# BATT_CPU.net
KiCad netlist of a schematic drawn in EAGLE
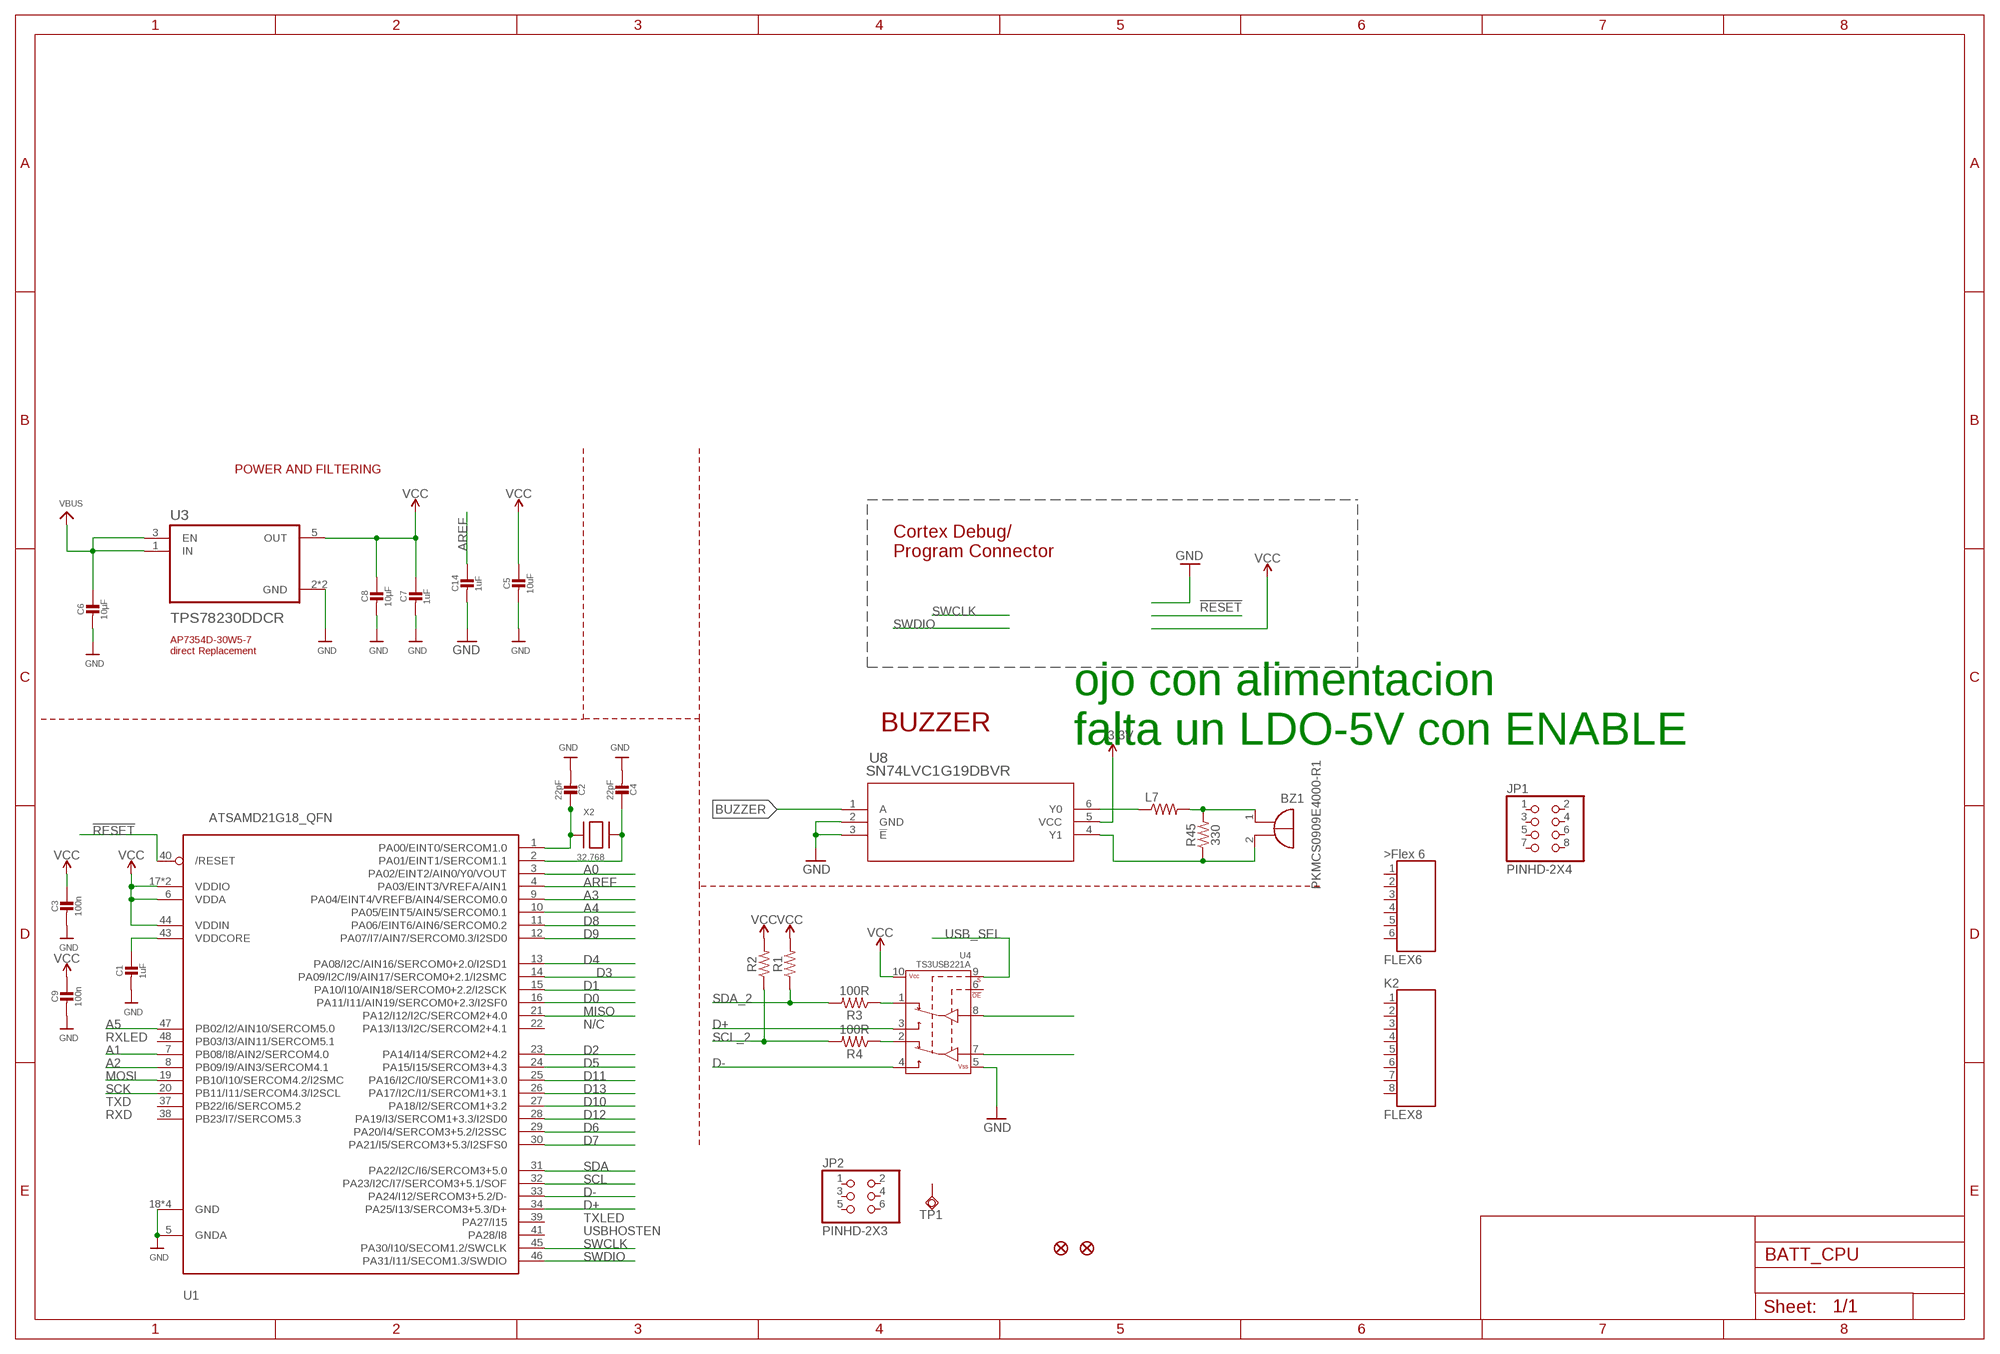
[diagram p0: schematic, sheet 1]

(export (version "E")
  (design (tool "Eeschema 10.0.6"))
  (components
    (comp (ref "BZ1")
      (value "PKMCS0909E4000-R1")
      (footprint "eagle-import:PKMCS0909")
      (libsource (lib "eagle-import") (part "PKMCS0909E4000-R1"))
    )
    (comp (ref "C1")
      (value "1uF")
      (footprint "eagle-import:0603-NO")
      (libsource (lib "eagle-import") (part "CAP_CERAMIC0603_NO"))
    )
    (comp (ref "C2")
      (value "22pF")
      (footprint "eagle-import:0603-NO")
      (libsource (lib "eagle-import") (part "CAP_CERAMIC0603_NO"))
    )
    (comp (ref "C3")
      (value "100n")
      (footprint "eagle-import:0603-NO")
      (libsource (lib "eagle-import") (part "CAP_CERAMIC0603_NO"))
    )
    (comp (ref "C4")
      (value "22pF")
      (footprint "eagle-import:0603-NO")
      (libsource (lib "eagle-import") (part "CAP_CERAMIC0603_NO"))
    )
    (comp (ref "C5")
      (value "10uF")
      (footprint "eagle-import:0805-NO")
      (libsource (lib "eagle-import") (part "CAP_CERAMIC0805-NOOUTLINE"))
    )
    (comp (ref "C6")
      (value "10µF")
      (footprint "eagle-import:0805-NO")
      (libsource (lib "eagle-import") (part "CAP_CERAMIC0805-NOOUTLINE"))
    )
    (comp (ref "C7")
      (value "1uF")
      (footprint "eagle-import:0603-NO")
      (libsource (lib "eagle-import") (part "CAP_CERAMIC0603_NO"))
    )
    (comp (ref "C8")
      (value "10µF")
      (footprint "eagle-import:0805-NO")
      (libsource (lib "eagle-import") (part "CAP_CERAMIC0805-NOOUTLINE"))
    )
    (comp (ref "C9")
      (value "100n")
      (footprint "eagle-import:0603-NO")
      (libsource (lib "eagle-import") (part "CAP_CERAMIC0603_NO"))
    )
    (comp (ref "C14")
      (value "1uF")
      (footprint "eagle-import:0603-NO")
      (libsource (lib "eagle-import") (part "CAP_CERAMIC0603_NO"))
    )
    (comp (ref "JP1")
      (value "PINHD-2X4")
      (footprint "eagle-import:2X04")
      (libsource (lib "eagle-import") (part "PINHD-2X4"))
    )
    (comp (ref "JP2")
      (value "PINHD-2X3")
      (footprint "eagle-import:2X03")
      (libsource (lib "eagle-import") (part "PINHD-2X3"))
    )
    (comp (ref "K1")
      (value "FLEX6")
      (footprint "eagle-import:FLEX6")
      (libsource (lib "eagle-import") (part "FLEX6"))
    )
    (comp (ref "K2")
      (value "FLEX8")
      (footprint "eagle-import:FLEX8")
      (libsource (lib "eagle-import") (part "FLEX8"))
    )
    (comp (ref "L7")
      (value "MMZ2012Y202BT000")
      (footprint "eagle-import:0805")
      (libsource (lib "eagle-import") (part "RESISTOR0805-RES"))
    )
    (comp (ref "R1")
      (value "RESISTOR0603")
      (footprint "eagle-import:0603")
      (libsource (lib "eagle-import") (part "RESISTOR0603"))
    )
    (comp (ref "R2")
      (value "RESISTOR0603")
      (footprint "eagle-import:0603")
      (libsource (lib "eagle-import") (part "RESISTOR0603"))
    )
    (comp (ref "R3")
      (value "100R")
      (footprint "eagle-import:0603")
      (libsource (lib "eagle-import") (part "RESISTOR0603"))
    )
    (comp (ref "R4")
      (value "100R")
      (footprint "eagle-import:0603")
      (libsource (lib "eagle-import") (part "RESISTOR0603"))
    )
    (comp (ref "R45")
      (value "330")
      (footprint "eagle-import:0805")
      (libsource (lib "eagle-import") (part "RESISTOR0805"))
    )
    (comp (ref "TP1")
      (value "TESTPAD_TPSQB1,27")
      (footprint "eagle-import:TESTPAD_B1,27")
      (libsource (lib "eagle-import") (part "TESTPAD_TPSQB1,27"))
    )
    (comp (ref "U$34")
      (value "FIDUCIAL\"\"")
      (footprint "eagle-import:FIDUCIAL_1MM")
      (libsource (lib "eagle-import") (part "FIDUCIAL{dblquote}{dblquote}"))
    )
    (comp (ref "U$35")
      (value "FIDUCIAL\"\"")
      (footprint "eagle-import:FIDUCIAL_1MM")
      (libsource (lib "eagle-import") (part "FIDUCIAL{dblquote}{dblquote}"))
    )
    (comp (ref "U1")
      (value "ATSAMD21G18_QFN")
      (footprint "eagle-import:TQFN48_7MM")
      (libsource (lib "eagle-import") (part "ATSAMD21J_QFN"))
    )
    (comp (ref "U3")
      (value "TPS78230DDCR")
      (footprint "eagle-import:SOT95P280X110-5N")
      (fields (field (name "MF") "Texas Instruments"))
      (libsource (lib "eagle-import") (part "TPS78230DDCR"))
    )
    (comp (ref "U4")
      (value "TS3USB221A")
      (footprint "eagle-import:QFN-10-RSE")
      (libsource (lib "eagle-import") (part "TS3USB221A"))
    )
    (comp (ref "U8")
      (value "SN74LVC1G19DBVR")
      (footprint "eagle-import:DBV6")
      (fields
        (field (name "GENERIC_PART_NUMBER") "SN74LVC1G19")
        (field (name "MANUFACTURER") "Texas Instruments")
      )
      (libsource (lib "eagle-import") (part "SN74LVC1G19DBVR"))
    )
    (comp (ref "X2")
      (value "32.768")
      (footprint "eagle-import:XTAL3215")
      (libsource (lib "eagle-import") (part "XTAL-3.2X1.5"))
    )
  )
  (nets
    (net (code "1") (name "/A0") (class "Default")
      (node (ref "U1") (pin "3") (pinfunction "PA02/EINT2/AIN0/Y0/VOUT_3") (pintype "bidirectional"))
    )
    (net (code "2") (name "/A1") (class "Default")
      (node (ref "U1") (pin "7") (pinfunction "PB08/I8/AIN2/SERCOM4.0_7") (pintype "bidirectional"))
    )
    (net (code "3") (name "/A2") (class "Default")
      (node (ref "U1") (pin "8") (pinfunction "PB09/I9/AIN3/SERCOM4.1_8") (pintype "bidirectional"))
    )
    (net (code "4") (name "/A3") (class "Default")
      (node (ref "U1") (pin "9") (pinfunction "PA04/EINT4/VREFB/AIN4/SERCOM0.0_9") (pintype "bidirectional"))
    )
    (net (code "5") (name "/A4") (class "Default")
      (node (ref "U1") (pin "10") (pinfunction "PA05/EINT5/AIN5/SERCOM0.1_10") (pintype "bidirectional"))
    )
    (net (code "6") (name "/A5") (class "Default")
      (node (ref "U1") (pin "47") (pinfunction "PB02/I2/AIN10/SERCOM5.0_47") (pintype "bidirectional"))
    )
    (net (code "7") (name "/AREF") (class "Default")
      (node (ref "C14") (pin "1") (pinfunction "1_1") (pintype "passive"))
      (node (ref "U1") (pin "4") (pinfunction "PA03/EINT3/VREFA/AIN1_4") (pintype "bidirectional"))
    )
    (net (code "8") (name "/D+") (class "Default")
      (node (ref "U1") (pin "34") (pinfunction "PA25/I13/SERCOM3+5.3/D+_34") (pintype "bidirectional"))
      (node (ref "U4") (pin "3") (pinfunction "2D+_3") (pintype "bidirectional"))
    )
    (net (code "9") (name "/D-") (class "Default")
      (node (ref "U1") (pin "33") (pinfunction "PA24/I12/SERCOM3+5.2/D-_33") (pintype "bidirectional"))
      (node (ref "U4") (pin "4") (pinfunction "2D-_4") (pintype "bidirectional"))
    )
    (net (code "10") (name "/D0") (class "Default")
      (node (ref "U1") (pin "16") (pinfunction "PA11/I11/AIN19/SERCOM0+2.3/I2SF0_16") (pintype "bidirectional"))
    )
    (net (code "11") (name "/D1") (class "Default")
      (node (ref "U1") (pin "15") (pinfunction "PA10/I10/AIN18/SERCOM0+2.2/I2SCK_15") (pintype "bidirectional"))
    )
    (net (code "12") (name "/D2") (class "Default")
      (node (ref "U1") (pin "23") (pinfunction "PA14/I14/SERCOM2+4.2_23") (pintype "bidirectional"))
    )
    (net (code "13") (name "/D3") (class "Default")
      (node (ref "U1") (pin "14") (pinfunction "PA09/I2C/I9/AIN17/SERCOM0+2.1/I2SMC_14") (pintype "bidirectional"))
    )
    (net (code "14") (name "/D4") (class "Default")
      (node (ref "U1") (pin "13") (pinfunction "PA08/I2C/AIN16/SERCOM0+2.0/I2SD1_13") (pintype "bidirectional"))
    )
    (net (code "15") (name "/D5") (class "Default")
      (node (ref "U1") (pin "24") (pinfunction "PA15/I15/SERCOM3+4.3_24") (pintype "bidirectional"))
    )
    (net (code "16") (name "/D6") (class "Default")
      (node (ref "U1") (pin "29") (pinfunction "PA20/I4/SERCOM3+5.2/I2SSC_29") (pintype "bidirectional"))
    )
    (net (code "17") (name "/D7") (class "Default")
      (node (ref "U1") (pin "30") (pinfunction "PA21/I5/SERCOM3+5.3/I2SFS0_30") (pintype "bidirectional"))
    )
    (net (code "18") (name "/D8") (class "Default")
      (node (ref "U1") (pin "11") (pinfunction "PA06/EINT6/AIN6/SERCOM0.2_11") (pintype "bidirectional"))
    )
    (net (code "19") (name "/D9") (class "Default")
      (node (ref "U1") (pin "12") (pinfunction "PA07/I7/AIN7/SERCOM0.3/I2SD0_12") (pintype "bidirectional"))
    )
    (net (code "20") (name "/D10") (class "Default")
      (node (ref "U1") (pin "27") (pinfunction "PA18/I2/SERCOM1+3.2_27") (pintype "bidirectional"))
    )
    (net (code "21") (name "/D11") (class "Default")
      (node (ref "U1") (pin "25") (pinfunction "PA16/I2C/I0/SERCOM1+3.0_25") (pintype "bidirectional"))
    )
    (net (code "22") (name "/D12") (class "Default")
      (node (ref "U1") (pin "28") (pinfunction "PA19/I3/SERCOM1+3.3/I2SD0_28") (pintype "bidirectional"))
    )
    (net (code "23") (name "/D13") (class "Default")
      (node (ref "U1") (pin "26") (pinfunction "PA17/I2C/I1/SERCOM1+3.1_26") (pintype "bidirectional"))
    )
    (net (code "24") (name "/MISO") (class "Default")
      (node (ref "U1") (pin "21") (pinfunction "PA12/I12/I2C/SERCOM2+4.0_21") (pintype "bidirectional"))
    )
    (net (code "25") (name "/MOSI") (class "Default")
      (node (ref "U1") (pin "19") (pinfunction "PB10/I10/SERCOM4.2/I2SMC_19") (pintype "bidirectional"))
    )
    (net (code "26") (name "/SCK") (class "Default")
      (node (ref "U1") (pin "20") (pinfunction "PB11/I11/SERCOM4.3/I2SCL_20") (pintype "bidirectional"))
    )
    (net (code "27") (name "/SCL") (class "Default")
      (node (ref "U1") (pin "32") (pinfunction "PA23/I2C/I7/SERCOM3+5.1/SOF_32") (pintype "bidirectional"))
    )
    (net (code "28") (name "/SCL_2") (class "Default")
      (node (ref "R2") (pin "1") (pinfunction "1_1") (pintype "passive"))
      (node (ref "R4") (pin "2") (pinfunction "2_2") (pintype "passive"))
    )
    (net (code "29") (name "/SDA") (class "Default")
      (node (ref "U1") (pin "31") (pinfunction "PA22/I2C/I6/SERCOM3+5.0_31") (pintype "bidirectional"))
    )
    (net (code "30") (name "/SDA_2") (class "Default")
      (node (ref "R1") (pin "1") (pinfunction "1_1") (pintype "passive"))
      (node (ref "R3") (pin "2") (pinfunction "2_2") (pintype "passive"))
    )
    (net (code "31") (name "/SWCLK") (class "Default")
      (node (ref "U1") (pin "45") (pinfunction "PA30/I10/SECOM1.2/SWCLK_45") (pintype "bidirectional"))
    )
    (net (code "32") (name "/SWDIO") (class "Default")
      (node (ref "U1") (pin "46") (pinfunction "PA31/I11/SECOM1.3/SWDIO_46") (pintype "bidirectional"))
    )
    (net (code "33") (name "/USB_SEL") (class "Default")
      (node (ref "U4") (pin "9") (pinfunction "S_9") (pintype "bidirectional"))
    )
    (net (code "34") (name "/~{RESET}") (class "Default")
      (node (ref "U1") (pin "40") (pinfunction "/RESET_40") (pintype "bidirectional"))
    )
    (net (code "35") (name "3.3V") (class "Default")
      (node (ref "U8") (pin "5") (pinfunction "VCC_5") (pintype "power_in"))
    )
    (net (code "36") (name "BUZZER") (class "Default")
      (node (ref "U8") (pin "1") (pinfunction "A_1") (pintype "input"))
    )
    (net (code "37") (name "GND") (class "Default")
      (node (ref "C1") (pin "2") (pinfunction "2_2") (pintype "passive"))
      (node (ref "C14") (pin "2") (pinfunction "2_2") (pintype "passive"))
      (node (ref "C2") (pin "2") (pinfunction "2_2") (pintype "passive"))
      (node (ref "C3") (pin "2") (pinfunction "2_2") (pintype "passive"))
      (node (ref "C4") (pin "2") (pinfunction "2_2") (pintype "passive"))
      (node (ref "C5") (pin "2") (pinfunction "2_2") (pintype "passive"))
      (node (ref "C6") (pin "2") (pinfunction "2_2") (pintype "passive"))
      (node (ref "C7") (pin "2") (pinfunction "2_2") (pintype "passive"))
      (node (ref "C8") (pin "2") (pinfunction "2_2") (pintype "passive"))
      (node (ref "C9") (pin "2") (pinfunction "2_2") (pintype "passive"))
      (node (ref "U1") (pin "18") (pinfunction "GND_18") (pintype "power_in"))
      (node (ref "U1") (pin "35") (pinfunction "GND_35") (pintype "power_in"))
      (node (ref "U1") (pin "42") (pinfunction "GND_42") (pintype "power_in"))
      (node (ref "U1") (pin "5") (pinfunction "GNDA_5") (pintype "power_in"))
      (node (ref "U1") (pin "THERMAL") (pinfunction "GND_THERMAL") (pintype "power_in"))
      (node (ref "U3") (pin "2") (pinfunction "GND_2") (pintype "power_in"))
      (node (ref "U3") (pin "4") (pinfunction "GND_4") (pintype "power_in"))
      (node (ref "U4") (pin "5") (pinfunction "VSS_5") (pintype "bidirectional"))
      (node (ref "U8") (pin "2") (pinfunction "GND_2") (pintype "power_in"))
      (node (ref "U8") (pin "3") (pinfunction "~{E}_3") (pintype "input"))
    )
    (net (code "38") (name "Net-(BZ1-+)") (class "Default")
      (node (ref "BZ1") (pin "1") (pinfunction "+_1") (pintype "passive"))
      (node (ref "L7") (pin "2") (pinfunction "2_2") (pintype "passive"))
      (node (ref "R45") (pin "2") (pinfunction "2_2") (pintype "passive"))
    )
    (net (code "39") (name "Net-(BZ1--)") (class "Default")
      (node (ref "BZ1") (pin "2") (pinfunction "-_2") (pintype "passive"))
      (node (ref "R45") (pin "1") (pinfunction "1_1") (pintype "passive"))
      (node (ref "U8") (pin "4") (pinfunction "Y1_4") (pintype "output"))
    )
    (net (code "40") (name "Net-(U1-PA00{slash}EINT0{slash}SERCOM1.0)") (class "Default")
      (node (ref "C2") (pin "1") (pinfunction "1_1") (pintype "passive"))
      (node (ref "U1") (pin "1") (pinfunction "PA00/EINT0/SERCOM1.0_1") (pintype "bidirectional"))
      (node (ref "X2") (pin "P$1") (pinfunction "P$1_P$1") (pintype "bidirectional"))
    )
    (net (code "41") (name "Net-(U1-PA01{slash}EINT1{slash}SERCOM1.1)") (class "Default")
      (node (ref "C4") (pin "1") (pinfunction "1_1") (pintype "passive"))
      (node (ref "U1") (pin "2") (pinfunction "PA01/EINT1/SERCOM1.1_2") (pintype "bidirectional"))
      (node (ref "X2") (pin "P$2") (pinfunction "P$2_P$2") (pintype "bidirectional"))
    )
    (net (code "42") (name "Net-(U1-VDDCORE)") (class "Default")
      (node (ref "C1") (pin "1") (pinfunction "1_1") (pintype "passive"))
      (node (ref "U1") (pin "43") (pinfunction "VDDCORE_43") (pintype "power_in"))
    )
    (net (code "43") (name "Net-(U4-1D+)") (class "Default")
      (node (ref "R3") (pin "1") (pinfunction "1_1") (pintype "passive"))
      (node (ref "U4") (pin "1") (pinfunction "1D+_1") (pintype "bidirectional"))
    )
    (net (code "44") (name "Net-(U4-1D-)") (class "Default")
      (node (ref "R4") (pin "1") (pinfunction "1_1") (pintype "passive"))
      (node (ref "U4") (pin "2") (pinfunction "1D-_2") (pintype "bidirectional"))
    )
    (net (code "45") (name "Net-(U8-Y0)") (class "Default")
      (node (ref "L7") (pin "1") (pinfunction "1_1") (pintype "passive"))
      (node (ref "U8") (pin "6") (pinfunction "Y0_6") (pintype "output"))
    )
    (net (code "46") (name "VBUS") (class "Default")
      (node (ref "C6") (pin "1") (pinfunction "1_1") (pintype "passive"))
      (node (ref "U3") (pin "1") (pinfunction "IN_1") (pintype "input"))
      (node (ref "U3") (pin "3") (pinfunction "EN_3") (pintype "input"))
    )
    (net (code "47") (name "VCC") (class "Default")
      (node (ref "C3") (pin "1") (pinfunction "1_1") (pintype "passive"))
      (node (ref "C5") (pin "1") (pinfunction "1_1") (pintype "passive"))
      (node (ref "C7") (pin "1") (pinfunction "1_1") (pintype "passive"))
      (node (ref "C8") (pin "1") (pinfunction "1_1") (pintype "passive"))
      (node (ref "C9") (pin "1") (pinfunction "1_1") (pintype "passive"))
      (node (ref "R1") (pin "2") (pinfunction "2_2") (pintype "passive"))
      (node (ref "R2") (pin "2") (pinfunction "2_2") (pintype "passive"))
      (node (ref "U1") (pin "17") (pinfunction "VDDIO_17") (pintype "power_in"))
      (node (ref "U1") (pin "36") (pinfunction "VDDIO_36") (pintype "power_in"))
      (node (ref "U1") (pin "44") (pinfunction "VDDIN_44") (pintype "power_in"))
      (node (ref "U1") (pin "6") (pinfunction "VDDA_6") (pintype "power_in"))
      (node (ref "U3") (pin "5") (pinfunction "OUT_5") (pintype "output"))
      (node (ref "U4") (pin "10") (pinfunction "VCC_10") (pintype "bidirectional"))
    )
    (net (code "48") (name "unconnected-(JP1-Pad1)") (class "Default")
      (node (ref "JP1") (pin "1") (pinfunction "1_1") (pintype "passive"))
    )
    (net (code "49") (name "unconnected-(JP1-Pad2)") (class "Default")
      (node (ref "JP1") (pin "2") (pinfunction "2_2") (pintype "passive"))
    )
    (net (code "50") (name "unconnected-(JP1-Pad3)") (class "Default")
      (node (ref "JP1") (pin "3") (pinfunction "3_3") (pintype "passive"))
    )
    (net (code "51") (name "unconnected-(JP1-Pad4)") (class "Default")
      (node (ref "JP1") (pin "4") (pinfunction "4_4") (pintype "passive"))
    )
    (net (code "52") (name "unconnected-(JP1-Pad5)") (class "Default")
      (node (ref "JP1") (pin "5") (pinfunction "5_5") (pintype "passive"))
    )
    (net (code "53") (name "unconnected-(JP1-Pad6)") (class "Default")
      (node (ref "JP1") (pin "6") (pinfunction "6_6") (pintype "passive"))
    )
    (net (code "54") (name "unconnected-(JP1-Pad7)") (class "Default")
      (node (ref "JP1") (pin "7") (pinfunction "7_7") (pintype "passive"))
    )
    (net (code "55") (name "unconnected-(JP1-Pad8)") (class "Default")
      (node (ref "JP1") (pin "8") (pinfunction "8_8") (pintype "passive"))
    )
    (net (code "56") (name "unconnected-(JP2-Pad1)") (class "Default")
      (node (ref "JP2") (pin "1") (pinfunction "1_1") (pintype "passive"))
    )
    (net (code "57") (name "unconnected-(JP2-Pad2)") (class "Default")
      (node (ref "JP2") (pin "2") (pinfunction "2_2") (pintype "passive"))
    )
    (net (code "58") (name "unconnected-(JP2-Pad3)") (class "Default")
      (node (ref "JP2") (pin "3") (pinfunction "3_3") (pintype "passive"))
    )
    (net (code "59") (name "unconnected-(JP2-Pad4)") (class "Default")
      (node (ref "JP2") (pin "4") (pinfunction "4_4") (pintype "passive"))
    )
    (net (code "60") (name "unconnected-(JP2-Pad5)") (class "Default")
      (node (ref "JP2") (pin "5") (pinfunction "5_5") (pintype "passive"))
    )
    (net (code "61") (name "unconnected-(JP2-Pad6)") (class "Default")
      (node (ref "JP2") (pin "6") (pinfunction "6_6") (pintype "passive"))
    )
    (net (code "62") (name "unconnected-(K1-Pad1)") (class "Default")
      (node (ref "K1") (pin "1") (pinfunction "1_1") (pintype "passive"))
    )
    (net (code "63") (name "unconnected-(K1-Pad2)") (class "Default")
      (node (ref "K1") (pin "2") (pinfunction "2_2") (pintype "passive"))
    )
    (net (code "64") (name "unconnected-(K1-Pad3)") (class "Default")
      (node (ref "K1") (pin "3") (pinfunction "3_3") (pintype "passive"))
    )
    (net (code "65") (name "unconnected-(K1-Pad4)") (class "Default")
      (node (ref "K1") (pin "4") (pinfunction "4_4") (pintype "passive"))
    )
    (net (code "66") (name "unconnected-(K1-Pad5)") (class "Default")
      (node (ref "K1") (pin "5") (pinfunction "5_5") (pintype "passive"))
    )
    (net (code "67") (name "unconnected-(K1-Pad6)") (class "Default")
      (node (ref "K1") (pin "6") (pinfunction "6_6") (pintype "passive"))
    )
    (net (code "68") (name "unconnected-(K2-Pad1)") (class "Default")
      (node (ref "K2") (pin "1") (pinfunction "1_1") (pintype "passive"))
    )
    (net (code "69") (name "unconnected-(K2-Pad2)") (class "Default")
      (node (ref "K2") (pin "2") (pinfunction "2_2") (pintype "passive"))
    )
    (net (code "70") (name "unconnected-(K2-Pad3)") (class "Default")
      (node (ref "K2") (pin "3") (pinfunction "3_3") (pintype "passive"))
    )
    (net (code "71") (name "unconnected-(K2-Pad4)") (class "Default")
      (node (ref "K2") (pin "4") (pinfunction "4_4") (pintype "passive"))
    )
    (net (code "72") (name "unconnected-(K2-Pad5)") (class "Default")
      (node (ref "K2") (pin "5") (pinfunction "5_5") (pintype "passive"))
    )
    (net (code "73") (name "unconnected-(K2-Pad6)") (class "Default")
      (node (ref "K2") (pin "6") (pinfunction "6_6") (pintype "passive"))
    )
    (net (code "74") (name "unconnected-(K2-Pad7)") (class "Default")
      (node (ref "K2") (pin "7") (pinfunction "7_7") (pintype "passive"))
    )
    (net (code "75") (name "unconnected-(K2-Pad8)") (class "Default")
      (node (ref "K2") (pin "8") (pinfunction "8_8") (pintype "passive"))
    )
    (net (code "76") (name "unconnected-(TP1-PadTP)") (class "Default")
      (node (ref "TP1") (pin "TP") (pinfunction "TP_TP") (pintype "input"))
    )
    (net (code "77") (name "unconnected-(U1-PA13{slash}I13{slash}I2C{slash}SERCOM2+4.1-Pad22)") (class "Default")
      (node (ref "U1") (pin "22") (pinfunction "PA13/I13/I2C/SERCOM2+4.1_22") (pintype "bidirectional"))
    )
    (net (code "78") (name "unconnected-(U1-PA27{slash}I15-Pad39)") (class "Default")
      (node (ref "U1") (pin "39") (pinfunction "PA27/I15_39") (pintype "bidirectional"))
    )
    (net (code "79") (name "unconnected-(U1-PA28{slash}I8-Pad41)") (class "Default")
      (node (ref "U1") (pin "41") (pinfunction "PA28/I8_41") (pintype "bidirectional"))
    )
    (net (code "80") (name "unconnected-(U1-PB03{slash}I3{slash}AIN11{slash}SERCOM5.1-Pad48)") (class "Default")
      (node (ref "U1") (pin "48") (pinfunction "PB03/I3/AIN11/SERCOM5.1_48") (pintype "bidirectional"))
    )
    (net (code "81") (name "unconnected-(U1-PB22{slash}I6{slash}SERCOM5.2-Pad37)") (class "Default")
      (node (ref "U1") (pin "37") (pinfunction "PB22/I6/SERCOM5.2_37") (pintype "bidirectional"))
    )
    (net (code "82") (name "unconnected-(U1-PB23{slash}I7{slash}SERCOM5.3-Pad38)") (class "Default")
      (node (ref "U1") (pin "38") (pinfunction "PB23/I7/SERCOM5.3_38") (pintype "bidirectional"))
    )
    (net (code "83") (name "unconnected-(U4-D+-Pad8)") (class "Default")
      (node (ref "U4") (pin "8") (pinfunction "D+_8") (pintype "bidirectional"))
    )
    (net (code "84") (name "unconnected-(U4-D--Pad7)") (class "Default")
      (node (ref "U4") (pin "7") (pinfunction "D-_7") (pintype "bidirectional"))
    )
    (net (code "85") (name "unconnected-(U4-~{OE}-Pad6)") (class "Default")
      (node (ref "U4") (pin "6") (pinfunction "~{OE}_6") (pintype "bidirectional"))
    )
  )
)
